# tiny430-2.net
KiCad netlist of a schematic drawn in EAGLE
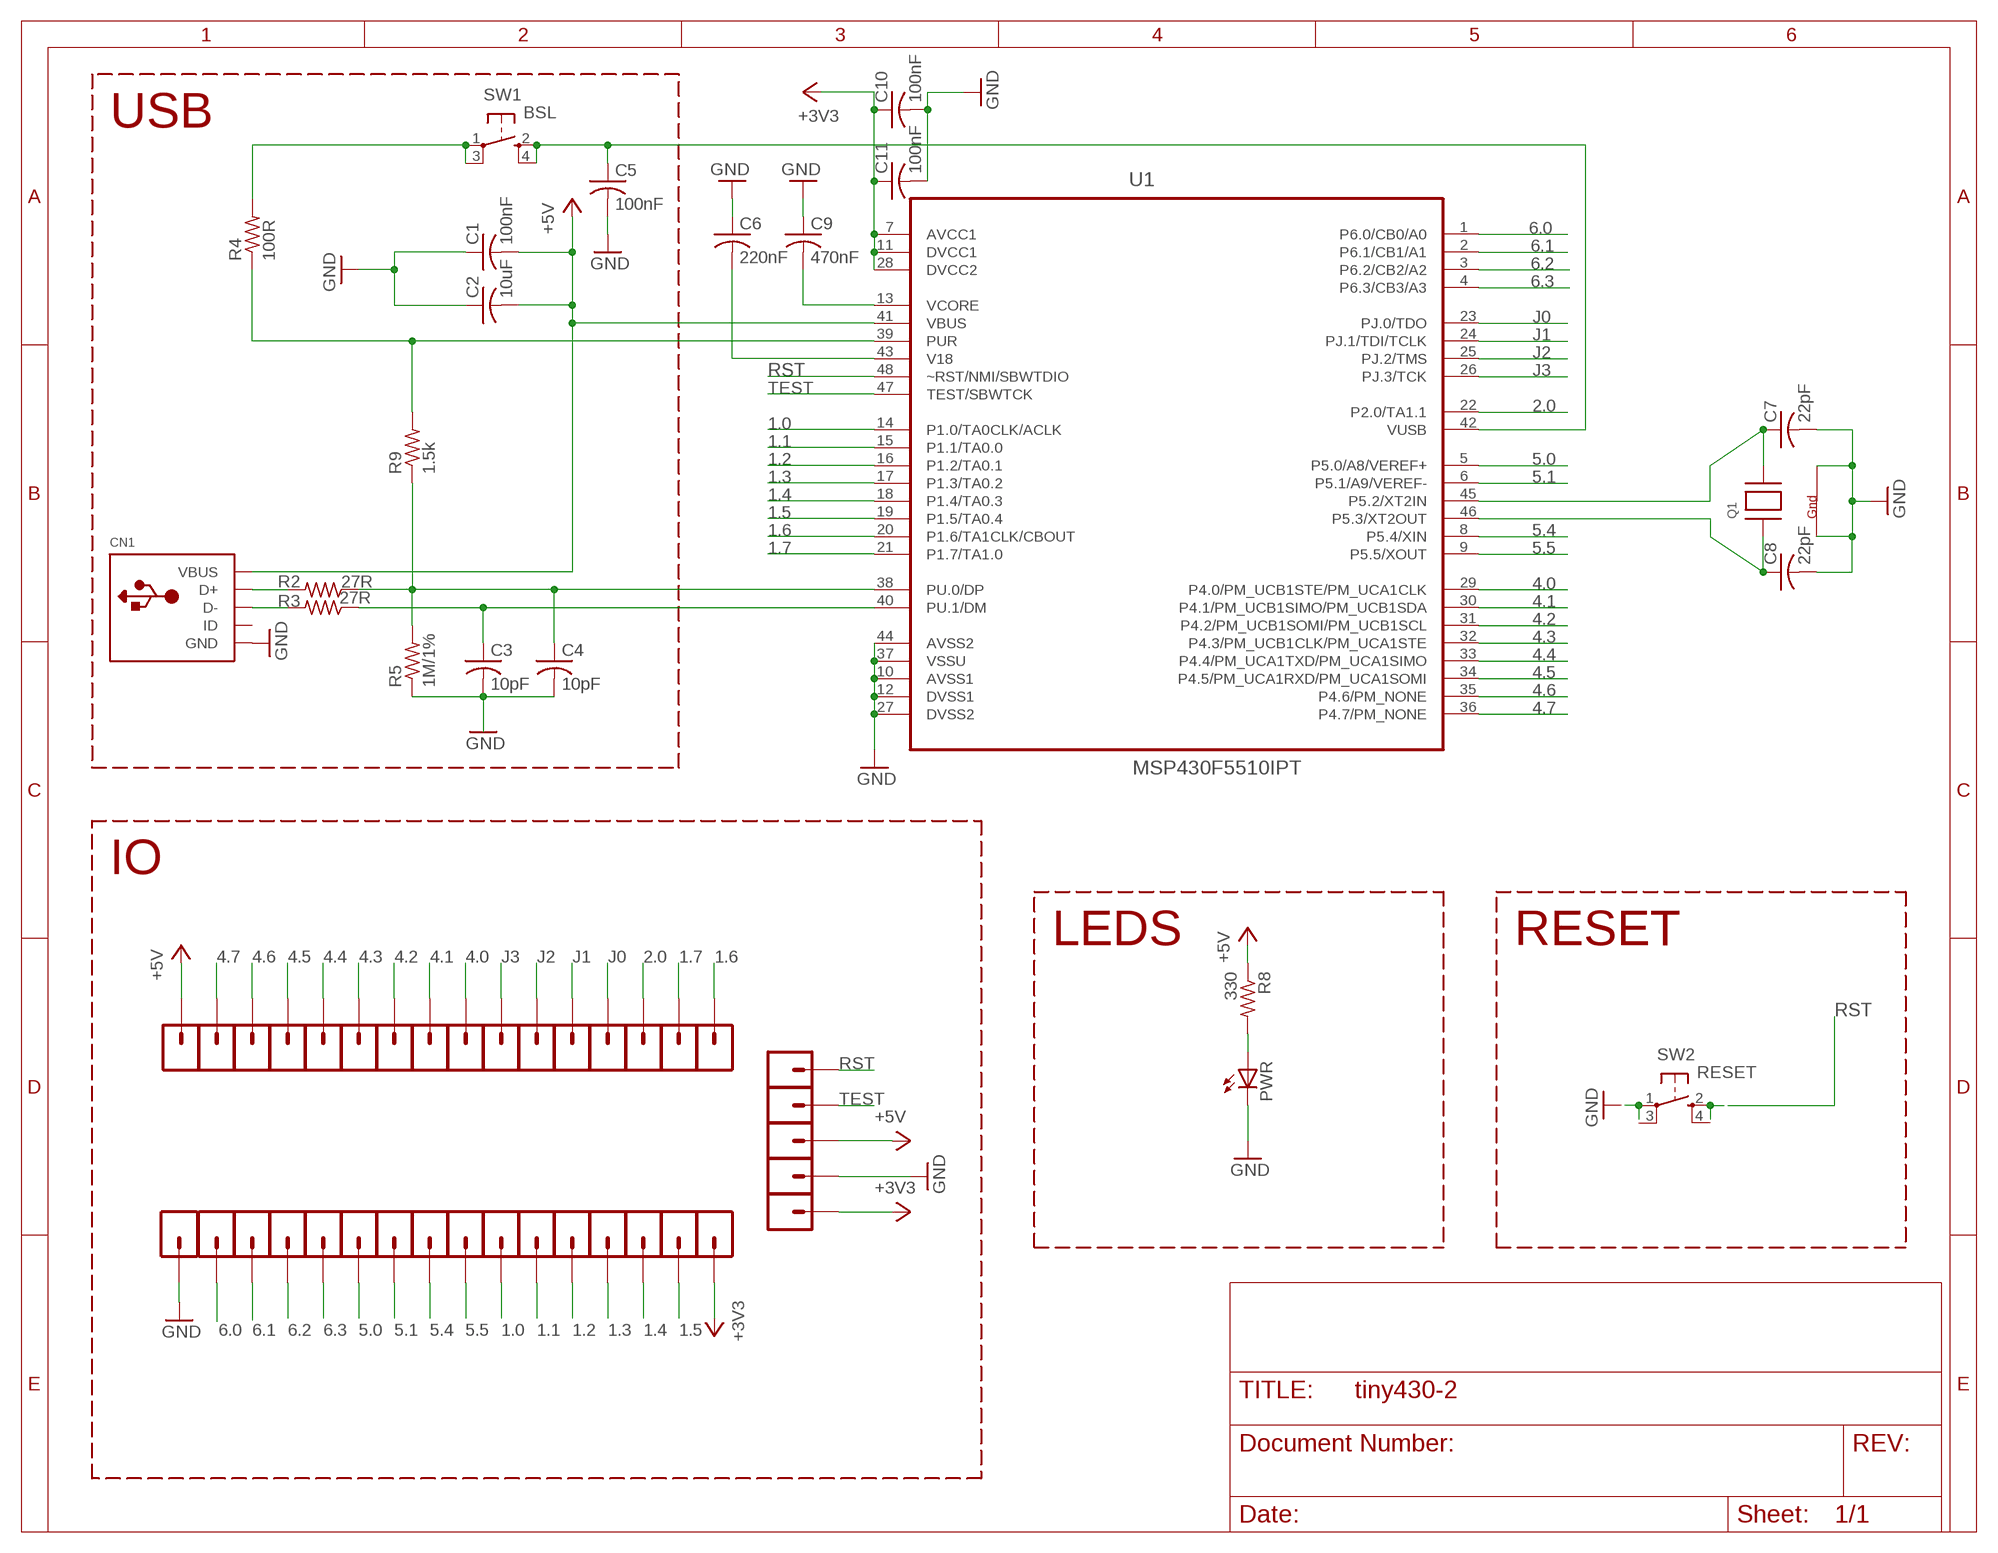
[diagram p0: schematic, sheet 1]

(export (version "E")
  (design (tool "Eeschema 10.0.6"))
  (components
    (comp (ref "C1")
      (value "100nF")
      (footprint "eagle-import:C0603K")
      (libsource (lib "eagle-import") (part "C-USC0603K"))
    )
    (comp (ref "C2")
      (value "10uF")
      (footprint "eagle-import:C0603K")
      (libsource (lib "eagle-import") (part "C-USC0603K"))
    )
    (comp (ref "C3")
      (value "10pF")
      (footprint "eagle-import:C0402K")
      (libsource (lib "eagle-import") (part "C-USC0402K"))
    )
    (comp (ref "C4")
      (value "10pF")
      (footprint "eagle-import:C0402K")
      (libsource (lib "eagle-import") (part "C-USC0402K"))
    )
    (comp (ref "C5")
      (value "100nF")
      (footprint "eagle-import:C0603K")
      (libsource (lib "eagle-import") (part "C-USC0603K"))
    )
    (comp (ref "C6")
      (value "220nF")
      (footprint "eagle-import:C0402K")
      (libsource (lib "eagle-import") (part "C-USC0402K"))
    )
    (comp (ref "C7")
      (value "22pF")
      (footprint "eagle-import:C0402K")
      (libsource (lib "eagle-import") (part "C-USC0402K"))
    )
    (comp (ref "C8")
      (value "22pF")
      (footprint "eagle-import:C0402K")
      (libsource (lib "eagle-import") (part "C-USC0402K"))
    )
    (comp (ref "C9")
      (value "470nF")
      (footprint "eagle-import:C0402K")
      (libsource (lib "eagle-import") (part "C-USC0402K"))
    )
    (comp (ref "C10")
      (value "100nF")
      (footprint "eagle-import:C0603K")
      (libsource (lib "eagle-import") (part "C-USC0603K"))
    )
    (comp (ref "C11")
      (value "100nF")
      (footprint "eagle-import:C0603K")
      (libsource (lib "eagle-import") (part "C-USC0603K"))
    )
    (comp (ref "CN1")
      (value "USBMINIB")
      (footprint "eagle-import:USB-MINIB")
      (libsource (lib "eagle-import") (part "USBMINIB"))
    )
    (comp (ref "JP1")
      (value "M01SMDNS")
      (footprint "eagle-import:1X01NS")
      (libsource (lib "eagle-import") (part "M01SMDNS"))
    )
    (comp (ref "JP2")
      (value "GND")
      (footprint "eagle-import:1X01NS")
      (libsource (lib "eagle-import") (part "M01SMDNS"))
    )
    (comp (ref "JP3")
      (value "M01SMDNS")
      (footprint "eagle-import:1X01NS")
      (libsource (lib "eagle-import") (part "M01SMDNS"))
    )
    (comp (ref "JP4")
      (value "M01SMDNS")
      (footprint "eagle-import:1X01NS")
      (libsource (lib "eagle-import") (part "M01SMDNS"))
    )
    (comp (ref "JP5")
      (value "M01SMDNS")
      (footprint "eagle-import:1X01NS")
      (libsource (lib "eagle-import") (part "M01SMDNS"))
    )
    (comp (ref "JP6")
      (value "M01SMDNS")
      (footprint "eagle-import:1X01NS")
      (libsource (lib "eagle-import") (part "M01SMDNS"))
    )
    (comp (ref "JP7")
      (value "M01SMDNS")
      (footprint "eagle-import:1X01NS")
      (libsource (lib "eagle-import") (part "M01SMDNS"))
    )
    (comp (ref "JP8")
      (value "M01SMDNS")
      (footprint "eagle-import:1X01NS")
      (libsource (lib "eagle-import") (part "M01SMDNS"))
    )
    (comp (ref "JP9")
      (value "M01SMDNS")
      (footprint "eagle-import:1X01NS")
      (libsource (lib "eagle-import") (part "M01SMDNS"))
    )
    (comp (ref "JP10")
      (value "M01SMDNS")
      (footprint "eagle-import:1X01NS")
      (libsource (lib "eagle-import") (part "M01SMDNS"))
    )
    (comp (ref "JP11")
      (value "M01SMDNS")
      (footprint "eagle-import:1X01NS")
      (libsource (lib "eagle-import") (part "M01SMDNS"))
    )
    (comp (ref "JP12")
      (value "M01SMDNS")
      (footprint "eagle-import:1X01NS")
      (libsource (lib "eagle-import") (part "M01SMDNS"))
    )
    (comp (ref "JP13")
      (value "M01SMDNS")
      (footprint "eagle-import:1X01NS")
      (libsource (lib "eagle-import") (part "M01SMDNS"))
    )
    (comp (ref "JP14")
      (value "M01SMDNS")
      (footprint "eagle-import:1X01NS")
      (libsource (lib "eagle-import") (part "M01SMDNS"))
    )
    (comp (ref "JP15")
      (value "M01SMDNS")
      (footprint "eagle-import:1X01NS")
      (libsource (lib "eagle-import") (part "M01SMDNS"))
    )
    (comp (ref "JP16")
      (value "M01SMDNS")
      (footprint "eagle-import:1X01NS")
      (libsource (lib "eagle-import") (part "M01SMDNS"))
    )
    (comp (ref "JP17")
      (value "M01SMDNS")
      (footprint "eagle-import:1X01NS")
      (libsource (lib "eagle-import") (part "M01SMDNS"))
    )
    (comp (ref "JP18")
      (value "M01SMDNS")
      (footprint "eagle-import:1X01NS")
      (libsource (lib "eagle-import") (part "M01SMDNS"))
    )
    (comp (ref "JP19")
      (value "M01SMDNS")
      (footprint "eagle-import:1X01NS")
      (libsource (lib "eagle-import") (part "M01SMDNS"))
    )
    (comp (ref "JP20")
      (value "M01SMDNS")
      (footprint "eagle-import:1X01NS")
      (libsource (lib "eagle-import") (part "M01SMDNS"))
    )
    (comp (ref "JP21")
      (value "M01SMDNS")
      (footprint "eagle-import:1X01NS")
      (libsource (lib "eagle-import") (part "M01SMDNS"))
    )
    (comp (ref "JP22")
      (value "M01SMDNS")
      (footprint "eagle-import:1X01NS")
      (libsource (lib "eagle-import") (part "M01SMDNS"))
    )
    (comp (ref "JP23")
      (value "M01SMDNS")
      (footprint "eagle-import:1X01NS")
      (libsource (lib "eagle-import") (part "M01SMDNS"))
    )
    (comp (ref "JP24")
      (value "M01SMDNS")
      (footprint "eagle-import:1X01NS")
      (libsource (lib "eagle-import") (part "M01SMDNS"))
    )
    (comp (ref "JP25")
      (value "M01SMDNS")
      (footprint "eagle-import:1X01NS")
      (libsource (lib "eagle-import") (part "M01SMDNS"))
    )
    (comp (ref "JP26")
      (value "M01SMDNS")
      (footprint "eagle-import:1X01NS")
      (libsource (lib "eagle-import") (part "M01SMDNS"))
    )
    (comp (ref "JP27")
      (value "M01SMDNS")
      (footprint "eagle-import:1X01NS")
      (libsource (lib "eagle-import") (part "M01SMDNS"))
    )
    (comp (ref "JP28")
      (value "M01SMDNS")
      (footprint "eagle-import:1X01NS")
      (libsource (lib "eagle-import") (part "M01SMDNS"))
    )
    (comp (ref "JP29")
      (value "M01SMDNS")
      (footprint "eagle-import:1X01NS")
      (libsource (lib "eagle-import") (part "M01SMDNS"))
    )
    (comp (ref "JP30")
      (value "M01SMDNS")
      (footprint "eagle-import:1X01NS")
      (libsource (lib "eagle-import") (part "M01SMDNS"))
    )
    (comp (ref "JP31")
      (value "M01SMDNS")
      (footprint "eagle-import:1X01NS")
      (libsource (lib "eagle-import") (part "M01SMDNS"))
    )
    (comp (ref "JP32")
      (value "M01SMDNS")
      (footprint "eagle-import:1X01NS")
      (libsource (lib "eagle-import") (part "M01SMDNS"))
    )
    (comp (ref "JP33")
      (value "M01SMDNS")
      (footprint "eagle-import:1X01NS")
      (libsource (lib "eagle-import") (part "M01SMDNS"))
    )
    (comp (ref "JP34")
      (value "M01SMDNS")
      (footprint "eagle-import:1X01NS")
      (libsource (lib "eagle-import") (part "M01SMDNS"))
    )
    (comp (ref "JP35")
      (value "M01SMDNS")
      (footprint "eagle-import:1X01NS")
      (libsource (lib "eagle-import") (part "M01SMDNS"))
    )
    (comp (ref "JP36")
      (value "M01SMDNS")
      (footprint "eagle-import:1X01NS")
      (libsource (lib "eagle-import") (part "M01SMDNS"))
    )
    (comp (ref "JP37")
      (value "M01SMDNS")
      (footprint "eagle-import:1X01NS")
      (libsource (lib "eagle-import") (part "M01SMDNS"))
    )
    (comp (ref "PWR")
      (value "LEDCHIPLED_0603")
      (footprint "eagle-import:CHIPLED_0603")
      (libsource (lib "eagle-import") (part "LEDCHIPLED_0603"))
    )
    (comp (ref "Q1")
      (value "XTAL-4-3225")
      (footprint "eagle-import:NX3225")
      (libsource (lib "eagle-import") (part "XTAL-4-3225"))
    )
    (comp (ref "R2")
      (value "27R")
      (footprint "eagle-import:R0402")
      (libsource (lib "eagle-import") (part "R-US_R0402"))
    )
    (comp (ref "R3")
      (value "27R")
      (footprint "eagle-import:R0402")
      (libsource (lib "eagle-import") (part "R-US_R0402"))
    )
    (comp (ref "R4")
      (value "100R")
      (footprint "eagle-import:R0402")
      (libsource (lib "eagle-import") (part "R-US_R0402"))
    )
    (comp (ref "R5")
      (value "1M/1%")
      (footprint "eagle-import:R0402")
      (libsource (lib "eagle-import") (part "R-US_R0402"))
    )
    (comp (ref "R8")
      (value "330")
      (footprint "eagle-import:R0402")
      (libsource (lib "eagle-import") (part "R-US_R0402"))
    )
    (comp (ref "R9")
      (value "1.5k")
      (footprint "eagle-import:R0402")
      (libsource (lib "eagle-import") (part "R-US_R0402"))
    )
    (comp (ref "SW1")
      (value "BSL")
      (footprint "eagle-import:KMR2")
      (libsource (lib "eagle-import") (part "SPST_TACT-KMR2"))
    )
    (comp (ref "SW2")
      (value "RESET")
      (footprint "eagle-import:KMR2")
      (libsource (lib "eagle-import") (part "SPST_TACT-KMR2"))
    )
    (comp (ref "U1")
      (value "MSP430F5510IPT")
      (footprint "eagle-import:QFP50P900X900X160-48N")
      (libsource (lib "eagle-import") (part "MSP430F5510IPT"))
    )
  )
  (nets
    (net (code "1") (name "+3V3") (class "Default")
      (node (ref "C10") (pin "1") (pinfunction "1_1") (pintype "passive"))
      (node (ref "C11") (pin "1") (pinfunction "1_1") (pintype "passive"))
      (node (ref "JP17") (pin "1") (pinfunction "1_1") (pintype "passive"))
      (node (ref "JP22") (pin "1") (pinfunction "1_1") (pintype "passive"))
      (node (ref "U1") (pin "11") (pinfunction "DVCC1_11") (pintype "power_in"))
      (node (ref "U1") (pin "28") (pinfunction "DVCC2_28") (pintype "power_in"))
      (node (ref "U1") (pin "7") (pinfunction "AVCC1_7") (pintype "power_in"))
    )
    (net (code "2") (name "+5V") (class "Default")
      (node (ref "C1") (pin "2") (pinfunction "2_2") (pintype "passive"))
      (node (ref "C2") (pin "2") (pinfunction "2_2") (pintype "passive"))
      (node (ref "CN1") (pin "VBUS") (pinfunction "VBUS_VBUS") (pintype "power_in"))
      (node (ref "JP1") (pin "1") (pinfunction "1_1") (pintype "passive"))
      (node (ref "JP20") (pin "1") (pinfunction "1_1") (pintype "passive"))
      (node (ref "R8") (pin "1") (pinfunction "1_1") (pintype "passive"))
      (node (ref "U1") (pin "41") (pinfunction "VBUS_41") (pintype "input"))
    )
    (net (code "3") (name "/1.0") (class "Default")
      (node (ref "JP9") (pin "1") (pinfunction "1_1") (pintype "passive"))
      (node (ref "U1") (pin "14") (pinfunction "P1.0/TA0CLK/ACLK_14") (pintype "bidirectional"))
    )
    (net (code "4") (name "/1.1") (class "Default")
      (node (ref "JP10") (pin "1") (pinfunction "1_1") (pintype "passive"))
      (node (ref "U1") (pin "15") (pinfunction "P1.1/TA0.0_15") (pintype "bidirectional"))
    )
    (net (code "5") (name "/1.2") (class "Default")
      (node (ref "JP11") (pin "1") (pinfunction "1_1") (pintype "passive"))
      (node (ref "U1") (pin "16") (pinfunction "P1.2/TA0.1_16") (pintype "bidirectional"))
    )
    (net (code "6") (name "/1.3") (class "Default")
      (node (ref "JP12") (pin "1") (pinfunction "1_1") (pintype "passive"))
      (node (ref "U1") (pin "17") (pinfunction "P1.3/TA0.2_17") (pintype "bidirectional"))
    )
    (net (code "7") (name "/1.4") (class "Default")
      (node (ref "JP13") (pin "1") (pinfunction "1_1") (pintype "passive"))
      (node (ref "U1") (pin "18") (pinfunction "P1.4/TA0.3_18") (pintype "bidirectional"))
    )
    (net (code "8") (name "/1.5") (class "Default")
      (node (ref "JP14") (pin "1") (pinfunction "1_1") (pintype "passive"))
      (node (ref "U1") (pin "19") (pinfunction "P1.5/TA0.4_19") (pintype "bidirectional"))
    )
    (net (code "9") (name "/1.6") (class "Default")
      (node (ref "JP37") (pin "1") (pinfunction "1_1") (pintype "passive"))
      (node (ref "U1") (pin "20") (pinfunction "P1.6/TA1CLK/CBOUT_20") (pintype "bidirectional"))
    )
    (net (code "10") (name "/1.7") (class "Default")
      (node (ref "JP36") (pin "1") (pinfunction "1_1") (pintype "passive"))
      (node (ref "U1") (pin "21") (pinfunction "P1.7/TA1.0_21") (pintype "bidirectional"))
    )
    (net (code "11") (name "/2.0") (class "Default")
      (node (ref "JP35") (pin "1") (pinfunction "1_1") (pintype "passive"))
      (node (ref "U1") (pin "22") (pinfunction "P2.0/TA1.1_22") (pintype "bidirectional"))
    )
    (net (code "12") (name "/4.0") (class "Default")
      (node (ref "JP30") (pin "1") (pinfunction "1_1") (pintype "passive"))
      (node (ref "U1") (pin "29") (pinfunction "P4.0/PM_UCB1STE/PM_UCA1CLK_29") (pintype "bidirectional"))
    )
    (net (code "13") (name "/4.1") (class "Default")
      (node (ref "JP29") (pin "1") (pinfunction "1_1") (pintype "passive"))
      (node (ref "U1") (pin "30") (pinfunction "P4.1/PM_UCB1SIMO/PM_UCB1SDA_30") (pintype "bidirectional"))
    )
    (net (code "14") (name "/4.2") (class "Default")
      (node (ref "JP28") (pin "1") (pinfunction "1_1") (pintype "passive"))
      (node (ref "U1") (pin "31") (pinfunction "P4.2/PM_UCB1SOMI/PM_UCB1SCL_31") (pintype "bidirectional"))
    )
    (net (code "15") (name "/4.3") (class "Default")
      (node (ref "JP27") (pin "1") (pinfunction "1_1") (pintype "passive"))
      (node (ref "U1") (pin "32") (pinfunction "P4.3/PM_UCB1CLK/PM_UCA1STE_32") (pintype "bidirectional"))
    )
    (net (code "16") (name "/4.4") (class "Default")
      (node (ref "JP26") (pin "1") (pinfunction "1_1") (pintype "passive"))
      (node (ref "U1") (pin "33") (pinfunction "P4.4/PM_UCA1TXD/PM_UCA1SIMO_33") (pintype "bidirectional"))
    )
    (net (code "17") (name "/4.5") (class "Default")
      (node (ref "JP25") (pin "1") (pinfunction "1_1") (pintype "passive"))
      (node (ref "U1") (pin "34") (pinfunction "P4.5/PM_UCA1RXD/PM_UCA1SOMI_34") (pintype "bidirectional"))
    )
    (net (code "18") (name "/4.6") (class "Default")
      (node (ref "JP24") (pin "1") (pinfunction "1_1") (pintype "passive"))
      (node (ref "U1") (pin "35") (pinfunction "P4.6/PM_NONE_35") (pintype "bidirectional"))
    )
    (net (code "19") (name "/4.7") (class "Default")
      (node (ref "JP23") (pin "1") (pinfunction "1_1") (pintype "passive"))
      (node (ref "U1") (pin "36") (pinfunction "P4.7/PM_NONE_36") (pintype "bidirectional"))
    )
    (net (code "20") (name "/5.0") (class "Default")
      (node (ref "JP7") (pin "1") (pinfunction "1_1") (pintype "passive"))
      (node (ref "U1") (pin "5") (pinfunction "P5.0/A8/VEREF+_5") (pintype "bidirectional"))
    )
    (net (code "21") (name "/5.1") (class "Default")
      (node (ref "JP8") (pin "1") (pinfunction "1_1") (pintype "passive"))
      (node (ref "U1") (pin "6") (pinfunction "P5.1/A9/VEREF-_6") (pintype "bidirectional"))
    )
    (net (code "22") (name "/5.4") (class "Default")
      (node (ref "JP15") (pin "1") (pinfunction "1_1") (pintype "passive"))
      (node (ref "U1") (pin "8") (pinfunction "P5.4/XIN_8") (pintype "input"))
    )
    (net (code "23") (name "/5.5") (class "Default")
      (node (ref "JP16") (pin "1") (pinfunction "1_1") (pintype "passive"))
      (node (ref "U1") (pin "9") (pinfunction "P5.5/XOUT_9") (pintype "output"))
    )
    (net (code "24") (name "/6.0") (class "Default")
      (node (ref "JP3") (pin "1") (pinfunction "1_1") (pintype "passive"))
      (node (ref "U1") (pin "1") (pinfunction "P6.0/CB0/A0_1") (pintype "bidirectional"))
    )
    (net (code "25") (name "/6.1") (class "Default")
      (node (ref "JP4") (pin "1") (pinfunction "1_1") (pintype "passive"))
      (node (ref "U1") (pin "2") (pinfunction "P6.1/CB1/A1_2") (pintype "bidirectional"))
    )
    (net (code "26") (name "/6.2") (class "Default")
      (node (ref "JP5") (pin "1") (pinfunction "1_1") (pintype "passive"))
      (node (ref "U1") (pin "3") (pinfunction "P6.2/CB2/A2_3") (pintype "bidirectional"))
    )
    (net (code "27") (name "/6.3") (class "Default")
      (node (ref "JP6") (pin "1") (pinfunction "1_1") (pintype "passive"))
      (node (ref "U1") (pin "4") (pinfunction "P6.3/CB3/A3_4") (pintype "bidirectional"))
    )
    (net (code "28") (name "/J0") (class "Default")
      (node (ref "JP34") (pin "1") (pinfunction "1_1") (pintype "passive"))
      (node (ref "U1") (pin "23") (pinfunction "PJ.0/TDO_23") (pintype "bidirectional"))
    )
    (net (code "29") (name "/J1") (class "Default")
      (node (ref "JP33") (pin "1") (pinfunction "1_1") (pintype "passive"))
      (node (ref "U1") (pin "24") (pinfunction "PJ.1/TDI/TCLK_24") (pintype "bidirectional"))
    )
    (net (code "30") (name "/J2") (class "Default")
      (node (ref "JP32") (pin "1") (pinfunction "1_1") (pintype "passive"))
      (node (ref "U1") (pin "25") (pinfunction "PJ.2/TMS_25") (pintype "bidirectional"))
    )
    (net (code "31") (name "/J3") (class "Default")
      (node (ref "JP31") (pin "1") (pinfunction "1_1") (pintype "passive"))
      (node (ref "U1") (pin "26") (pinfunction "PJ.3/TCK_26") (pintype "bidirectional"))
    )
    (net (code "32") (name "/RST") (class "Default")
      (node (ref "JP18") (pin "1") (pinfunction "1_1") (pintype "passive"))
      (node (ref "SW2") (pin "2") (pinfunction "S_2") (pintype "passive"))
      (node (ref "SW2") (pin "4") (pinfunction "S1_4") (pintype "passive"))
      (node (ref "U1") (pin "48") (pinfunction "~{RST/NMI/SBWTDIO}_48") (pintype "input"))
    )
    (net (code "33") (name "/TEST") (class "Default")
      (node (ref "JP19") (pin "1") (pinfunction "1_1") (pintype "passive"))
      (node (ref "U1") (pin "47") (pinfunction "TEST/SBWTCK_47") (pintype "input"))
    )
    (net (code "34") (name "GND") (class "Default")
      (node (ref "C1") (pin "1") (pinfunction "1_1") (pintype "passive"))
      (node (ref "C10") (pin "2") (pinfunction "2_2") (pintype "passive"))
      (node (ref "C11") (pin "2") (pinfunction "2_2") (pintype "passive"))
      (node (ref "C2") (pin "1") (pinfunction "1_1") (pintype "passive"))
      (node (ref "C3") (pin "2") (pinfunction "2_2") (pintype "passive"))
      (node (ref "C4") (pin "2") (pinfunction "2_2") (pintype "passive"))
      (node (ref "C5") (pin "2") (pinfunction "2_2") (pintype "passive"))
      (node (ref "C6") (pin "1") (pinfunction "1_1") (pintype "passive"))
      (node (ref "C7") (pin "2") (pinfunction "2_2") (pintype "passive"))
      (node (ref "C8") (pin "2") (pinfunction "2_2") (pintype "passive"))
      (node (ref "C9") (pin "1") (pinfunction "1_1") (pintype "passive"))
      (node (ref "CN1") (pin "GND") (pinfunction "GND_GND") (pintype "power_in"))
      (node (ref "JP2") (pin "1") (pinfunction "1_1") (pintype "passive"))
      (node (ref "JP21") (pin "1") (pinfunction "1_1") (pintype "passive"))
      (node (ref "PWR") (pin "C") (pinfunction "C_C") (pintype "passive"))
      (node (ref "Q1") (pin "2") (pinfunction "G2_2") (pintype "power_in"))
      (node (ref "Q1") (pin "4") (pinfunction "G1_4") (pintype "power_in"))
      (node (ref "R5") (pin "1") (pinfunction "1_1") (pintype "passive"))
      (node (ref "SW2") (pin "1") (pinfunction "P_1") (pintype "passive"))
      (node (ref "SW2") (pin "3") (pinfunction "P1_3") (pintype "passive"))
      (node (ref "U1") (pin "10") (pinfunction "AVSS1_10") (pintype "passive"))
      (node (ref "U1") (pin "12") (pinfunction "DVSS1_12") (pintype "passive"))
      (node (ref "U1") (pin "27") (pinfunction "DVSS2_27") (pintype "passive"))
      (node (ref "U1") (pin "37") (pinfunction "VSSU_37") (pintype "passive"))
      (node (ref "U1") (pin "44") (pinfunction "AVSS2_44") (pintype "passive"))
    )
    (net (code "35") (name "Net-(CN1-PadD+)") (class "Default")
      (node (ref "CN1") (pin "D+") (pinfunction "D+_D+") (pintype "bidirectional"))
      (node (ref "R2") (pin "2") (pinfunction "2_2") (pintype "passive"))
    )
    (net (code "36") (name "Net-(CN1-PadD-)") (class "Default")
      (node (ref "CN1") (pin "D-") (pinfunction "D-_D-") (pintype "bidirectional"))
      (node (ref "R3") (pin "2") (pinfunction "2_2") (pintype "passive"))
    )
    (net (code "37") (name "Net-(PWR-PadA)") (class "Default")
      (node (ref "PWR") (pin "A") (pinfunction "A_A") (pintype "passive"))
      (node (ref "R8") (pin "2") (pinfunction "2_2") (pintype "passive"))
    )
    (net (code "38") (name "Net-(Q1-X1)") (class "Default")
      (node (ref "C8") (pin "1") (pinfunction "1_1") (pintype "passive"))
      (node (ref "Q1") (pin "1") (pinfunction "X1_1") (pintype "bidirectional"))
      (node (ref "U1") (pin "46") (pinfunction "P5.3/XT2OUT_46") (pintype "bidirectional"))
    )
    (net (code "39") (name "Net-(Q1-X2)") (class "Default")
      (node (ref "C7") (pin "1") (pinfunction "1_1") (pintype "passive"))
      (node (ref "Q1") (pin "3") (pinfunction "X2_3") (pintype "bidirectional"))
      (node (ref "U1") (pin "45") (pinfunction "P5.2/XT2IN_45") (pintype "bidirectional"))
    )
    (net (code "40") (name "Net-(SW1-P)") (class "Default")
      (node (ref "R4") (pin "2") (pinfunction "2_2") (pintype "passive"))
      (node (ref "SW1") (pin "1") (pinfunction "P_1") (pintype "passive"))
      (node (ref "SW1") (pin "3") (pinfunction "P1_3") (pintype "passive"))
    )
    (net (code "41") (name "Net-(SW1-S)") (class "Default")
      (node (ref "C5") (pin "1") (pinfunction "1_1") (pintype "passive"))
      (node (ref "SW1") (pin "2") (pinfunction "S_2") (pintype "passive"))
      (node (ref "SW1") (pin "4") (pinfunction "S1_4") (pintype "passive"))
      (node (ref "U1") (pin "42") (pinfunction "VUSB_42") (pintype "output"))
    )
    (net (code "42") (name "Net-(U1-PU.0{slash}DP)") (class "Default")
      (node (ref "C4") (pin "1") (pinfunction "1_1") (pintype "passive"))
      (node (ref "R2") (pin "1") (pinfunction "1_1") (pintype "passive"))
      (node (ref "R5") (pin "2") (pinfunction "2_2") (pintype "passive"))
      (node (ref "R9") (pin "1") (pinfunction "1_1") (pintype "passive"))
      (node (ref "U1") (pin "38") (pinfunction "PU.0/DP_38") (pintype "bidirectional"))
    )
    (net (code "43") (name "Net-(U1-PU.1{slash}DM)") (class "Default")
      (node (ref "C3") (pin "1") (pinfunction "1_1") (pintype "passive"))
      (node (ref "R3") (pin "1") (pinfunction "1_1") (pintype "passive"))
      (node (ref "U1") (pin "40") (pinfunction "PU.1/DM_40") (pintype "bidirectional"))
    )
    (net (code "44") (name "Net-(U1-PUR)") (class "Default")
      (node (ref "R4") (pin "1") (pinfunction "1_1") (pintype "passive"))
      (node (ref "R9") (pin "2") (pinfunction "2_2") (pintype "passive"))
      (node (ref "U1") (pin "39") (pinfunction "PUR_39") (pintype "bidirectional"))
    )
    (net (code "45") (name "Net-(U1-V18)") (class "Default")
      (node (ref "C6") (pin "2") (pinfunction "2_2") (pintype "passive"))
      (node (ref "U1") (pin "43") (pinfunction "V18_43") (pintype "input"))
    )
    (net (code "46") (name "Net-(U1-VCORE)") (class "Default")
      (node (ref "C9") (pin "2") (pinfunction "2_2") (pintype "passive"))
      (node (ref "U1") (pin "13") (pinfunction "VCORE_13") (pintype "input"))
    )
    (net (code "47") (name "unconnected-(CN1-PadID)") (class "Default")
      (node (ref "CN1") (pin "ID") (pinfunction "ID_ID") (pintype "bidirectional"))
    )
  )
)
